# gateway-motherboard.net
KiCad netlist of a schematic drawn in EAGLE
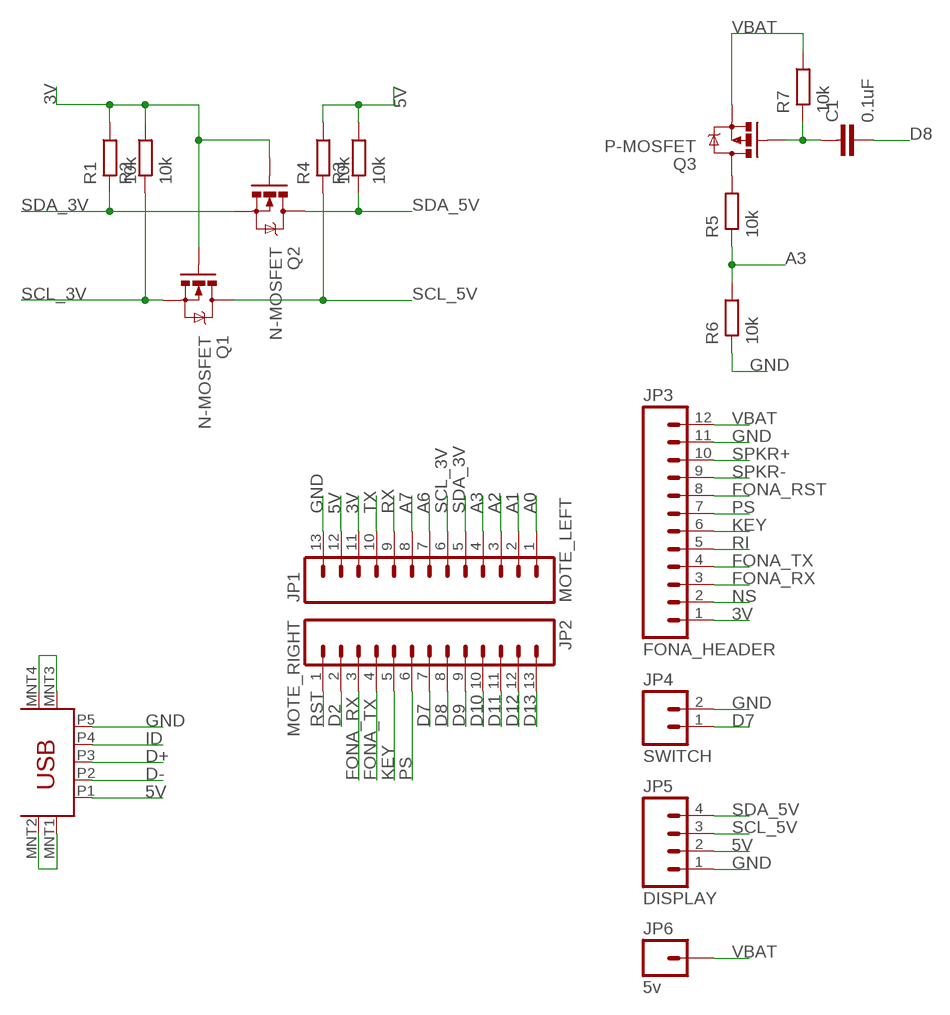
[diagram p0: schematic, sheet 1]

(export (version "E")
  (design (tool "Eeschema 10.0.6"))
  (components
    (comp (ref "C1")
      (value "0.1uF")
      (footprint "eagle-import:C0603-L")
      (libsource (lib "eagle-import") (part "CAPACITOR0603-L"))
    )
    (comp (ref "JP1")
      (value "MOTE_LEFT")
      (footprint "eagle-import:1X13-LONGPADS")
      (libsource (lib "eagle-import") (part "M13LONGPADS"))
    )
    (comp (ref "JP2")
      (value "MOTE_RIGHT")
      (footprint "eagle-import:1X13-LONGPADS")
      (libsource (lib "eagle-import") (part "M13LONGPADS"))
    )
    (comp (ref "JP3")
      (value "FONA_HEADER")
      (footprint "eagle-import:1X12_LONGPADS")
      (libsource (lib "eagle-import") (part "M12LONGPADS"))
    )
    (comp (ref "JP4")
      (value "SWITCH")
      (footprint "eagle-import:1X02_LOCK_LONGPADS")
      (libsource (lib "eagle-import") (part "M02LOCK_LONGPADS"))
    )
    (comp (ref "JP5")
      (value "DISPLAY")
      (footprint "eagle-import:1X04_LONGPADS")
      (libsource (lib "eagle-import") (part "M04LONGPADS"))
    )
    (comp (ref "JP6")
      (value "5v")
      (footprint "eagle-import:1X01NS-KIT")
      (libsource (lib "eagle-import") (part "M01NOSILK-KIT"))
    )
    (comp (ref "Q1")
      (value "N-MOSFET")
      (footprint "eagle-import:SOT23")
      (libsource (lib "eagle-import") (part "MOSFET-NCHANNELBSS138"))
    )
    (comp (ref "Q2")
      (value "N-MOSFET")
      (footprint "eagle-import:SOT23")
      (libsource (lib "eagle-import") (part "MOSFET-NCHANNELBSS138"))
    )
    (comp (ref "Q3")
      (value "P-MOSFET")
      (footprint "eagle-import:SOT23-3")
      (libsource (lib "eagle-import") (part "MOSFET-PCHANNELIRLML2244"))
    )
    (comp (ref "R1")
      (value "10k")
      (footprint "eagle-import:R0603-L")
      (libsource (lib "eagle-import") (part "RESISTOR0603-L"))
    )
    (comp (ref "R2")
      (value "10k")
      (footprint "eagle-import:R0603-L")
      (libsource (lib "eagle-import") (part "RESISTOR0603-L"))
    )
    (comp (ref "R3")
      (value "10k")
      (footprint "eagle-import:R0603-L")
      (libsource (lib "eagle-import") (part "RESISTOR0603-L"))
    )
    (comp (ref "R4")
      (value "10k")
      (footprint "eagle-import:R0603-L")
      (libsource (lib "eagle-import") (part "RESISTOR0603-L"))
    )
    (comp (ref "R5")
      (value "10k")
      (footprint "eagle-import:R0603-L")
      (libsource (lib "eagle-import") (part "RESISTOR0603-L"))
    )
    (comp (ref "R6")
      (value "10k")
      (footprint "eagle-import:R0603-L")
      (libsource (lib "eagle-import") (part "RESISTOR0603-L"))
    )
    (comp (ref "R7")
      (value "10k")
      (footprint "eagle-import:R0603-L")
      (libsource (lib "eagle-import") (part "RESISTOR0603-L"))
    )
    (comp (ref "U$1")
      (value "USB-MINIB")
      (footprint "eagle-import:USB-MINIB_HOLE_RETENTION")
      (libsource (lib "eagle-import") (part "USB-MINIB"))
    )
  )
  (nets
    (net (code "1") (name "/3V") (class "Default")
      (node (ref "JP1") (pin "11") (pinfunction "11_11") (pintype "passive"))
      (node (ref "JP3") (pin "1") (pinfunction "1_1") (pintype "passive"))
      (node (ref "Q1") (pin "1") (pinfunction "G_1") (pintype "passive"))
      (node (ref "Q2") (pin "1") (pinfunction "G_1") (pintype "passive"))
      (node (ref "R1") (pin "2") (pinfunction "P$2_2") (pintype "passive"))
      (node (ref "R2") (pin "2") (pinfunction "P$2_2") (pintype "passive"))
    )
    (net (code "2") (name "/5V") (class "Default")
      (node (ref "JP1") (pin "12") (pinfunction "12_12") (pintype "passive"))
      (node (ref "JP5") (pin "2") (pinfunction "2_2") (pintype "passive"))
      (node (ref "R3") (pin "2") (pinfunction "P$2_2") (pintype "passive"))
      (node (ref "R4") (pin "2") (pinfunction "P$2_2") (pintype "passive"))
      (node (ref "U$1") (pin "P1") (pinfunction "VBUS_P1") (pintype "bidirectional"))
    )
    (net (code "3") (name "/A0") (class "Default")
      (node (ref "JP1") (pin "1") (pinfunction "1_1") (pintype "passive"))
    )
    (net (code "4") (name "/A1") (class "Default")
      (node (ref "JP1") (pin "2") (pinfunction "2_2") (pintype "passive"))
    )
    (net (code "5") (name "/A2") (class "Default")
      (node (ref "JP1") (pin "3") (pinfunction "3_3") (pintype "passive"))
    )
    (net (code "6") (name "/A3") (class "Default")
      (node (ref "JP1") (pin "4") (pinfunction "4_4") (pintype "passive"))
      (node (ref "R5") (pin "1") (pinfunction "P$1_1") (pintype "passive"))
      (node (ref "R6") (pin "2") (pinfunction "P$2_2") (pintype "passive"))
    )
    (net (code "7") (name "/A6") (class "Default")
      (node (ref "JP1") (pin "7") (pinfunction "7_7") (pintype "passive"))
    )
    (net (code "8") (name "/A7") (class "Default")
      (node (ref "JP1") (pin "8") (pinfunction "8_8") (pintype "passive"))
    )
    (net (code "9") (name "/D+") (class "Default")
      (node (ref "U$1") (pin "P3") (pinfunction "D+_P3") (pintype "bidirectional"))
    )
    (net (code "10") (name "/D-") (class "Default")
      (node (ref "U$1") (pin "P2") (pinfunction "D-_P2") (pintype "bidirectional"))
    )
    (net (code "11") (name "/D2") (class "Default")
      (node (ref "JP2") (pin "2") (pinfunction "2_2") (pintype "passive"))
    )
    (net (code "12") (name "/D7") (class "Default")
      (node (ref "JP2") (pin "7") (pinfunction "7_7") (pintype "passive"))
      (node (ref "JP4") (pin "1") (pinfunction "1_1") (pintype "passive"))
    )
    (net (code "13") (name "/D8") (class "Default")
      (node (ref "C1") (pin "2") (pinfunction "2_2") (pintype "passive"))
      (node (ref "JP2") (pin "8") (pinfunction "8_8") (pintype "passive"))
    )
    (net (code "14") (name "/D9") (class "Default")
      (node (ref "JP2") (pin "9") (pinfunction "9_9") (pintype "passive"))
    )
    (net (code "15") (name "/D10") (class "Default")
      (node (ref "JP2") (pin "10") (pinfunction "10_10") (pintype "passive"))
    )
    (net (code "16") (name "/D11") (class "Default")
      (node (ref "JP2") (pin "11") (pinfunction "11_11") (pintype "passive"))
    )
    (net (code "17") (name "/D12") (class "Default")
      (node (ref "JP2") (pin "12") (pinfunction "12_12") (pintype "passive"))
    )
    (net (code "18") (name "/D13") (class "Default")
      (node (ref "JP2") (pin "13") (pinfunction "13_13") (pintype "passive"))
    )
    (net (code "19") (name "/FONA_RST") (class "Default")
      (node (ref "JP3") (pin "8") (pinfunction "8_8") (pintype "passive"))
    )
    (net (code "20") (name "/FONA_RX") (class "Default")
      (node (ref "JP2") (pin "3") (pinfunction "3_3") (pintype "passive"))
      (node (ref "JP3") (pin "3") (pinfunction "3_3") (pintype "passive"))
    )
    (net (code "21") (name "/FONA_TX") (class "Default")
      (node (ref "JP2") (pin "4") (pinfunction "4_4") (pintype "passive"))
      (node (ref "JP3") (pin "4") (pinfunction "4_4") (pintype "passive"))
    )
    (net (code "22") (name "/GND") (class "Default")
      (node (ref "JP1") (pin "13") (pinfunction "13_13") (pintype "passive"))
      (node (ref "JP3") (pin "11") (pinfunction "11_11") (pintype "passive"))
      (node (ref "JP4") (pin "2") (pinfunction "2_2") (pintype "passive"))
      (node (ref "JP5") (pin "1") (pinfunction "1_1") (pintype "passive"))
      (node (ref "R6") (pin "1") (pinfunction "P$1_1") (pintype "passive"))
      (node (ref "U$1") (pin "MNT1") (pinfunction "MTN1_MNT1") (pintype "bidirectional"))
      (node (ref "U$1") (pin "MNT2") (pinfunction "MTN2_MNT2") (pintype "bidirectional"))
      (node (ref "U$1") (pin "MNT3") (pinfunction "MTN3_MNT3") (pintype "bidirectional"))
      (node (ref "U$1") (pin "MNT4") (pinfunction "MTN4_MNT4") (pintype "bidirectional"))
      (node (ref "U$1") (pin "P5") (pinfunction "GND_P5") (pintype "bidirectional"))
    )
    (net (code "23") (name "/ID") (class "Default")
      (node (ref "U$1") (pin "P4") (pinfunction "ID_P4") (pintype "bidirectional"))
    )
    (net (code "24") (name "/KEY") (class "Default")
      (node (ref "JP2") (pin "5") (pinfunction "5_5") (pintype "passive"))
      (node (ref "JP3") (pin "6") (pinfunction "6_6") (pintype "passive"))
    )
    (net (code "25") (name "/NS") (class "Default")
      (node (ref "JP3") (pin "2") (pinfunction "2_2") (pintype "passive"))
    )
    (net (code "26") (name "/PS") (class "Default")
      (node (ref "JP2") (pin "6") (pinfunction "6_6") (pintype "passive"))
      (node (ref "JP3") (pin "7") (pinfunction "7_7") (pintype "passive"))
    )
    (net (code "27") (name "/RI") (class "Default")
      (node (ref "JP3") (pin "5") (pinfunction "5_5") (pintype "passive"))
    )
    (net (code "28") (name "/RST") (class "Default")
      (node (ref "JP2") (pin "1") (pinfunction "1_1") (pintype "passive"))
    )
    (net (code "29") (name "/RX") (class "Default")
      (node (ref "JP1") (pin "9") (pinfunction "9_9") (pintype "passive"))
    )
    (net (code "30") (name "/SCL_3V") (class "Default")
      (node (ref "JP1") (pin "6") (pinfunction "6_6") (pintype "passive"))
      (node (ref "Q1") (pin "2") (pinfunction "S_2") (pintype "passive"))
      (node (ref "R2") (pin "1") (pinfunction "P$1_1") (pintype "passive"))
    )
    (net (code "31") (name "/SCL_5V") (class "Default")
      (node (ref "JP5") (pin "3") (pinfunction "3_3") (pintype "passive"))
      (node (ref "Q1") (pin "3") (pinfunction "D_3") (pintype "passive"))
      (node (ref "R4") (pin "1") (pinfunction "P$1_1") (pintype "passive"))
    )
    (net (code "32") (name "/SDA_3V") (class "Default")
      (node (ref "JP1") (pin "5") (pinfunction "5_5") (pintype "passive"))
      (node (ref "Q2") (pin "2") (pinfunction "S_2") (pintype "passive"))
      (node (ref "R1") (pin "1") (pinfunction "P$1_1") (pintype "passive"))
    )
    (net (code "33") (name "/SDA_5V") (class "Default")
      (node (ref "JP5") (pin "4") (pinfunction "4_4") (pintype "passive"))
      (node (ref "Q2") (pin "3") (pinfunction "D_3") (pintype "passive"))
      (node (ref "R3") (pin "1") (pinfunction "P$1_1") (pintype "passive"))
    )
    (net (code "34") (name "/SPKR+") (class "Default")
      (node (ref "JP3") (pin "10") (pinfunction "10_10") (pintype "passive"))
    )
    (net (code "35") (name "/SPKR-") (class "Default")
      (node (ref "JP3") (pin "9") (pinfunction "9_9") (pintype "passive"))
    )
    (net (code "36") (name "/TX") (class "Default")
      (node (ref "JP1") (pin "10") (pinfunction "10_10") (pintype "passive"))
    )
    (net (code "37") (name "/VBAT") (class "Default")
      (node (ref "JP3") (pin "12") (pinfunction "12_12") (pintype "passive"))
      (node (ref "JP6") (pin "1") (pinfunction "1_1") (pintype "passive"))
      (node (ref "Q3") (pin "2") (pinfunction "S_2") (pintype "passive"))
      (node (ref "R7") (pin "2") (pinfunction "P$2_2") (pintype "passive"))
    )
    (net (code "38") (name "Net-(Q3-D)") (class "Default")
      (node (ref "Q3") (pin "3") (pinfunction "D_3") (pintype "passive"))
      (node (ref "R5") (pin "2") (pinfunction "P$2_2") (pintype "passive"))
    )
    (net (code "39") (name "Net-(Q3-G)") (class "Default")
      (node (ref "C1") (pin "1") (pinfunction "1_1") (pintype "passive"))
      (node (ref "Q3") (pin "1") (pinfunction "G_1") (pintype "passive"))
      (node (ref "R7") (pin "1") (pinfunction "P$1_1") (pintype "passive"))
    )
  )
)
